# rev3.net
KiCad netlist of a schematic drawn in EAGLE
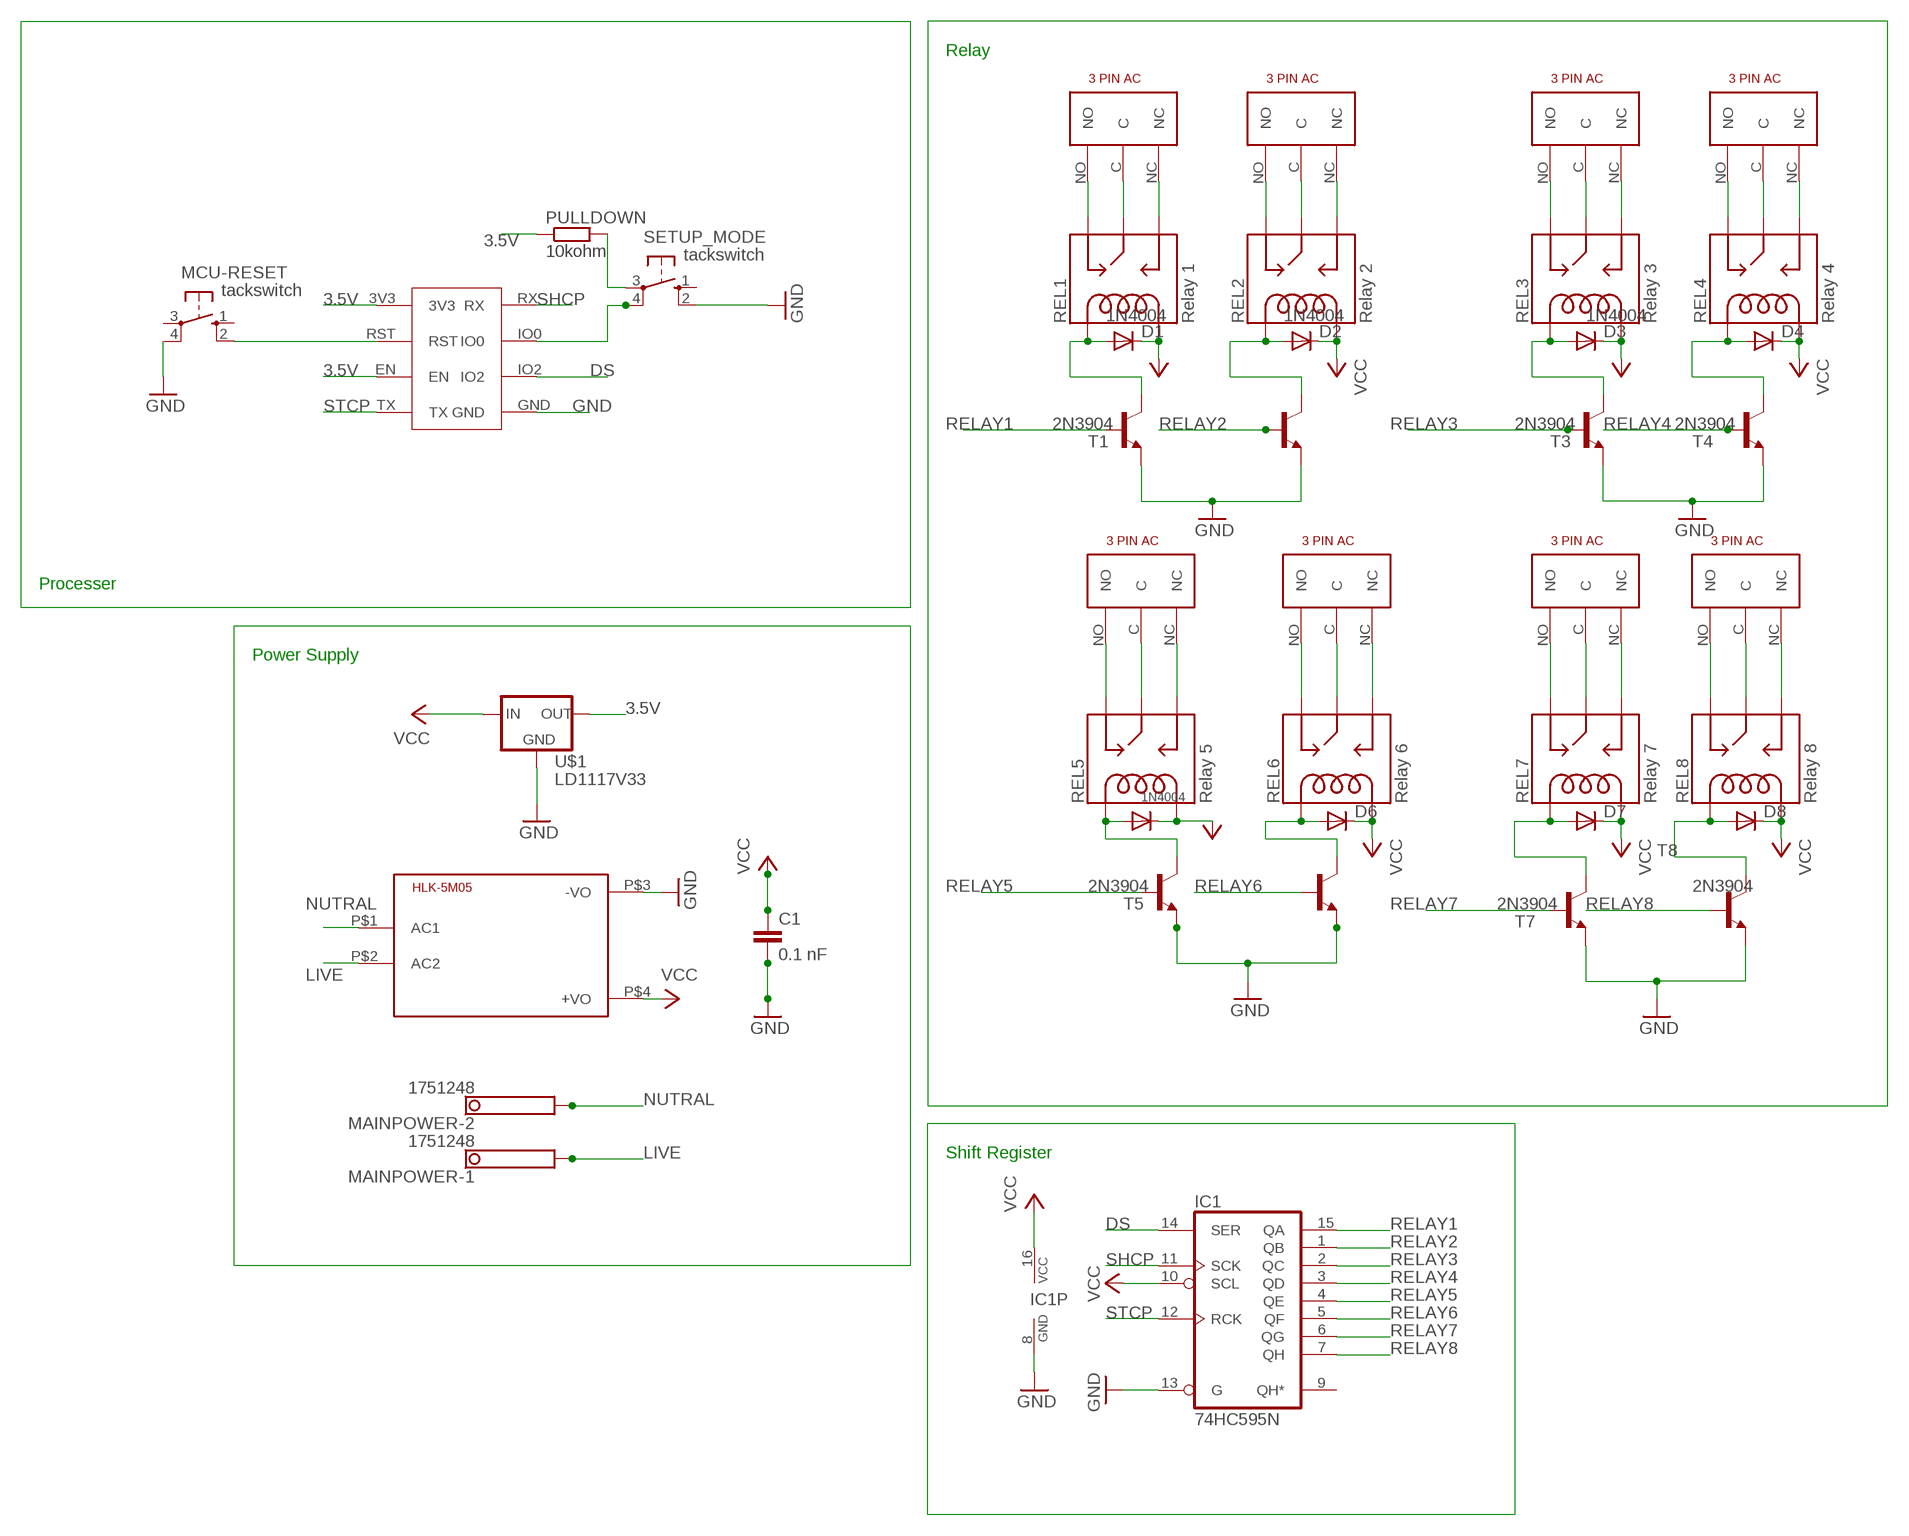
[diagram p0: schematic, sheet 1]

(export (version "E")
  (design (tool "Eeschema 10.0.6"))
  (components
    (comp (ref "C1")
      (value "0.1 nF")
      (footprint "eagle-import:CAP-PTH-SMALL-KIT")
      (libsource (lib "eagle-import") (part "0.1UF-KIT-EZ-50V-20%"))
    )
    (comp (ref "CON-REL-1")
      (value "3PINAC")
      (footprint "eagle-import:LIB")
      (libsource (lib "eagle-import") (part "3PINAC"))
    )
    (comp (ref "CON-REL-2")
      (value "3PINAC")
      (footprint "eagle-import:LIB")
      (libsource (lib "eagle-import") (part "3PINAC"))
    )
    (comp (ref "CON-REL-3")
      (value "3PINAC")
      (footprint "eagle-import:LIB")
      (libsource (lib "eagle-import") (part "3PINAC"))
    )
    (comp (ref "CON-REL-4")
      (value "3PINAC")
      (footprint "eagle-import:LIB")
      (libsource (lib "eagle-import") (part "3PINAC"))
    )
    (comp (ref "CON-REL-5")
      (value "3PINAC")
      (footprint "eagle-import:LIB")
      (libsource (lib "eagle-import") (part "3PINAC"))
    )
    (comp (ref "CON-REL-6")
      (value "3PINAC")
      (footprint "eagle-import:LIB")
      (libsource (lib "eagle-import") (part "3PINAC"))
    )
    (comp (ref "CON-REL-7")
      (value "3PINAC")
      (footprint "eagle-import:LIB")
      (libsource (lib "eagle-import") (part "3PINAC"))
    )
    (comp (ref "CON-REL-8")
      (value "3PINAC")
      (footprint "eagle-import:LIB")
      (libsource (lib "eagle-import") (part "3PINAC"))
    )
    (comp (ref "D1")
      (value "1N4004")
      (footprint "eagle-import:DO41-10")
      (libsource (lib "eagle-import") (part "1N4004"))
    )
    (comp (ref "D2")
      (value "1N4004")
      (footprint "eagle-import:DO41-10")
      (libsource (lib "eagle-import") (part "1N4004"))
    )
    (comp (ref "D3")
      (value "1N4004")
      (footprint "eagle-import:DO41-10")
      (libsource (lib "eagle-import") (part "1N4004"))
    )
    (comp (ref "D4")
      (value "1N4004")
      (footprint "eagle-import:DO41-10")
      (libsource (lib "eagle-import") (part "1N4004"))
    )
    (comp (ref "D5")
      (value "1N4004")
      (footprint "eagle-import:DO41-10")
      (libsource (lib "eagle-import") (part "1N4004"))
    )
    (comp (ref "D6")
      (value "1N4004")
      (footprint "eagle-import:DO41-10")
      (libsource (lib "eagle-import") (part "1N4004"))
    )
    (comp (ref "D7")
      (value "1N4004")
      (footprint "eagle-import:DO41-10")
      (libsource (lib "eagle-import") (part "1N4004"))
    )
    (comp (ref "D8")
      (value "1N4004")
      (footprint "eagle-import:DO41-10")
      (libsource (lib "eagle-import") (part "1N4004"))
    )
    (comp (ref "HLK-5M05")
      (value "AC to DC Converter")
      (footprint "eagle-import:HKLPM01")
      (libsource (lib "eagle-import") (part "HKLPM01"))
    )
    (comp (ref "IC1")
      (value "74HC595N")
      (footprint "eagle-import:DIL16")
      (libsource (lib "eagle-import") (part "74595NHC"))
    )
    (comp (ref "MAINPOWER")
      (value "1751248")
      (footprint "eagle-import:1751248")
      (libsource (lib "eagle-import") (part "1751248"))
    )
    (comp (ref "MCU-RESET")
      (value "tackswitch")
      (footprint "eagle-import:B3F-10XX")
      (libsource (lib "eagle-import") (part "10-XX"))
    )
    (comp (ref "PULLDOWN")
      (value "10kohm")
      (footprint "eagle-import:0204_7")
      (libsource (lib "eagle-import") (part "R-EU_0204/7"))
    )
    (comp (ref "REL1")
      (value "Relay 1")
      (footprint "eagle-import:SRD-05VDC-SL-C")
      (libsource (lib "eagle-import") (part "RELAYPTH"))
    )
    (comp (ref "REL2")
      (value "Relay 2")
      (footprint "eagle-import:SRD-05VDC-SL-C")
      (libsource (lib "eagle-import") (part "RELAYPTH"))
    )
    (comp (ref "REL3")
      (value "Relay 3")
      (footprint "eagle-import:SRD-05VDC-SL-C")
      (libsource (lib "eagle-import") (part "RELAYPTH"))
    )
    (comp (ref "REL4")
      (value "Relay 4")
      (footprint "eagle-import:SRD-05VDC-SL-C")
      (libsource (lib "eagle-import") (part "RELAYPTH"))
    )
    (comp (ref "REL5")
      (value "Relay 5")
      (footprint "eagle-import:SRD-05VDC-SL-C")
      (libsource (lib "eagle-import") (part "RELAYPTH"))
    )
    (comp (ref "REL6")
      (value "Relay 6")
      (footprint "eagle-import:SRD-05VDC-SL-C")
      (libsource (lib "eagle-import") (part "RELAYPTH"))
    )
    (comp (ref "REL7")
      (value "Relay 7")
      (footprint "eagle-import:SRD-05VDC-SL-C")
      (libsource (lib "eagle-import") (part "RELAYPTH"))
    )
    (comp (ref "REL8")
      (value "Relay 8")
      (footprint "eagle-import:SRD-05VDC-SL-C")
      (libsource (lib "eagle-import") (part "RELAYPTH"))
    )
    (comp (ref "SETUP_MODE")
      (value "tackswitch")
      (footprint "eagle-import:B3F-10XX")
      (libsource (lib "eagle-import") (part "10-XX"))
    )
    (comp (ref "T1")
      (value "2N3904")
      (footprint "eagle-import:TO92-EBC")
      (libsource (lib "eagle-import") (part "BC618"))
    )
    (comp (ref "T2")
      (value "2N3904")
      (footprint "eagle-import:TO92-EBC")
      (libsource (lib "eagle-import") (part "BC618"))
    )
    (comp (ref "T3")
      (value "2N3904")
      (footprint "eagle-import:TO92-EBC")
      (libsource (lib "eagle-import") (part "BC618"))
    )
    (comp (ref "T4")
      (value "2N3904")
      (footprint "eagle-import:TO92-EBC")
      (libsource (lib "eagle-import") (part "BC618"))
    )
    (comp (ref "T5")
      (value "2N3904")
      (footprint "eagle-import:TO92-EBC")
      (libsource (lib "eagle-import") (part "BC618"))
    )
    (comp (ref "T6")
      (value "2N3904")
      (footprint "eagle-import:TO92-EBC")
      (libsource (lib "eagle-import") (part "BC618"))
    )
    (comp (ref "T7")
      (value "2N3904")
      (footprint "eagle-import:TO92-EBC")
      (libsource (lib "eagle-import") (part "BC618"))
    )
    (comp (ref "T8")
      (value "2N3904")
      (footprint "eagle-import:TO92-EBC")
      (libsource (lib "eagle-import") (part "BC618"))
    )
    (comp (ref "U$1")
      (value "LD1117V33")
      (footprint "eagle-import:LD1117V33")
      (libsource (lib "eagle-import") (part "LD1117V33"))
    )
    (comp (ref "U$2")
      (value "ESP01")
      (footprint "eagle-import:ESP01")
      (libsource (lib "eagle-import") (part "ESP01"))
    )
  )
  (nets
    (net (code "1") (name "/3.5V") (class "Default")
      (node (ref "PULLDOWN") (pin "1") (pinfunction "1_1") (pintype "passive"))
      (node (ref "U$1") (pin "OUT") (pinfunction "OUT_OUT") (pintype "output"))
      (node (ref "U$2") (pin "3V3") (pinfunction "3V3_3V3") (pintype "bidirectional"))
      (node (ref "U$2") (pin "EN") (pinfunction "EN_EN") (pintype "bidirectional"))
    )
    (net (code "2") (name "/DS") (class "Default")
      (node (ref "IC1") (pin "14") (pinfunction "SER_14") (pintype "input"))
      (node (ref "U$2") (pin "IO2") (pinfunction "IO2_IO2") (pintype "bidirectional"))
    )
    (net (code "3") (name "/LIVE") (class "Default")
      (node (ref "HLK-5M05") (pin "P$2") (pinfunction "AC2_P$2") (pintype "bidirectional"))
      (node (ref "MAINPOWER") (pin "1") (pinfunction "K_1") (pintype "passive"))
    )
    (net (code "4") (name "/NUTRAL") (class "Default")
      (node (ref "HLK-5M05") (pin "P$1") (pinfunction "AC1_P$1") (pintype "bidirectional"))
      (node (ref "MAINPOWER") (pin "2") (pinfunction "K_2") (pintype "passive"))
    )
    (net (code "5") (name "/RELAY1") (class "Default")
      (node (ref "IC1") (pin "15") (pinfunction "QA_15") (pintype "tri_state"))
      (node (ref "T1") (pin "B") (pinfunction "B_B") (pintype "passive"))
    )
    (net (code "6") (name "/RELAY2") (class "Default")
      (node (ref "IC1") (pin "1") (pinfunction "QB_1") (pintype "tri_state"))
      (node (ref "T2") (pin "B") (pinfunction "B_B") (pintype "passive"))
    )
    (net (code "7") (name "/RELAY3") (class "Default")
      (node (ref "IC1") (pin "2") (pinfunction "QC_2") (pintype "tri_state"))
      (node (ref "T3") (pin "B") (pinfunction "B_B") (pintype "passive"))
    )
    (net (code "8") (name "/RELAY4") (class "Default")
      (node (ref "IC1") (pin "3") (pinfunction "QD_3") (pintype "tri_state"))
      (node (ref "T4") (pin "B") (pinfunction "B_B") (pintype "passive"))
    )
    (net (code "9") (name "/RELAY5") (class "Default")
      (node (ref "IC1") (pin "4") (pinfunction "QE_4") (pintype "tri_state"))
      (node (ref "T5") (pin "B") (pinfunction "B_B") (pintype "passive"))
    )
    (net (code "10") (name "/RELAY6") (class "Default")
      (node (ref "IC1") (pin "5") (pinfunction "QF_5") (pintype "tri_state"))
      (node (ref "T6") (pin "B") (pinfunction "B_B") (pintype "passive"))
    )
    (net (code "11") (name "/RELAY7") (class "Default")
      (node (ref "IC1") (pin "6") (pinfunction "QG_6") (pintype "tri_state"))
      (node (ref "T7") (pin "B") (pinfunction "B_B") (pintype "passive"))
    )
    (net (code "12") (name "/RELAY8") (class "Default")
      (node (ref "IC1") (pin "7") (pinfunction "QH_7") (pintype "tri_state"))
      (node (ref "T8") (pin "B") (pinfunction "B_B") (pintype "passive"))
    )
    (net (code "13") (name "/SHCP") (class "Default")
      (node (ref "IC1") (pin "11") (pinfunction "SCK_11") (pintype "input"))
      (node (ref "U$2") (pin "RX") (pinfunction "RX_RX") (pintype "bidirectional"))
    )
    (net (code "14") (name "/STCP") (class "Default")
      (node (ref "IC1") (pin "12") (pinfunction "RCK_12") (pintype "input"))
      (node (ref "U$2") (pin "TX") (pinfunction "TX_TX") (pintype "bidirectional"))
    )
    (net (code "15") (name "GND") (class "Default")
      (node (ref "C1") (pin "2") (pinfunction "2_2") (pintype "passive"))
      (node (ref "HLK-5M05") (pin "P$3") (pinfunction "-VO_P$3") (pintype "bidirectional"))
      (node (ref "IC1") (pin "13") (pinfunction "G_13") (pintype "input"))
      (node (ref "IC1") (pin "8") (pinfunction "GND_8") (pintype "power_in"))
      (node (ref "MCU-RESET") (pin "4") (pinfunction "P1_4") (pintype "passive"))
      (node (ref "SETUP_MODE") (pin "2") (pinfunction "S1_2") (pintype "passive"))
      (node (ref "T1") (pin "E") (pinfunction "E_E") (pintype "passive"))
      (node (ref "T2") (pin "E") (pinfunction "E_E") (pintype "passive"))
      (node (ref "T3") (pin "E") (pinfunction "E_E") (pintype "passive"))
      (node (ref "T4") (pin "E") (pinfunction "E_E") (pintype "passive"))
      (node (ref "T5") (pin "E") (pinfunction "E_E") (pintype "passive"))
      (node (ref "T6") (pin "E") (pinfunction "E_E") (pintype "passive"))
      (node (ref "T7") (pin "E") (pinfunction "E_E") (pintype "passive"))
      (node (ref "T8") (pin "E") (pinfunction "E_E") (pintype "passive"))
      (node (ref "U$1") (pin "GND") (pinfunction "GND_GND") (pintype "input"))
      (node (ref "U$2") (pin "GND") (pinfunction "GND_GND") (pintype "bidirectional"))
    )
    (net (code "16") (name "Net-(CON-REL-1-PadC)") (class "Default")
      (node (ref "CON-REL-1") (pin "C") (pinfunction "C_C") (pintype "bidirectional"))
      (node (ref "REL1") (pin "SWCOMMON") (pinfunction "SWCOMMON_SWCOMMON") (pintype "bidirectional"))
    )
    (net (code "17") (name "Net-(CON-REL-1-PadNC)") (class "Default")
      (node (ref "CON-REL-1") (pin "NC") (pinfunction "NC_NC") (pintype "bidirectional"))
      (node (ref "REL1") (pin "SWOPEN") (pinfunction "SWOPEN_SWOPEN") (pintype "bidirectional"))
    )
    (net (code "18") (name "Net-(CON-REL-2-PadC)") (class "Default")
      (node (ref "CON-REL-2") (pin "C") (pinfunction "C_C") (pintype "bidirectional"))
      (node (ref "REL2") (pin "SWCOMMON") (pinfunction "SWCOMMON_SWCOMMON") (pintype "bidirectional"))
    )
    (net (code "19") (name "Net-(CON-REL-2-PadNC)") (class "Default")
      (node (ref "CON-REL-2") (pin "NC") (pinfunction "NC_NC") (pintype "bidirectional"))
      (node (ref "REL2") (pin "SWOPEN") (pinfunction "SWOPEN_SWOPEN") (pintype "bidirectional"))
    )
    (net (code "20") (name "Net-(CON-REL-3-PadC)") (class "Default")
      (node (ref "CON-REL-3") (pin "C") (pinfunction "C_C") (pintype "bidirectional"))
      (node (ref "REL3") (pin "SWCOMMON") (pinfunction "SWCOMMON_SWCOMMON") (pintype "bidirectional"))
    )
    (net (code "21") (name "Net-(CON-REL-3-PadNC)") (class "Default")
      (node (ref "CON-REL-3") (pin "NC") (pinfunction "NC_NC") (pintype "bidirectional"))
      (node (ref "REL3") (pin "SWOPEN") (pinfunction "SWOPEN_SWOPEN") (pintype "bidirectional"))
    )
    (net (code "22") (name "Net-(CON-REL-4-PadC)") (class "Default")
      (node (ref "CON-REL-4") (pin "C") (pinfunction "C_C") (pintype "bidirectional"))
      (node (ref "REL4") (pin "SWCOMMON") (pinfunction "SWCOMMON_SWCOMMON") (pintype "bidirectional"))
    )
    (net (code "23") (name "Net-(CON-REL-4-PadNC)") (class "Default")
      (node (ref "CON-REL-4") (pin "NC") (pinfunction "NC_NC") (pintype "bidirectional"))
      (node (ref "REL4") (pin "SWOPEN") (pinfunction "SWOPEN_SWOPEN") (pintype "bidirectional"))
    )
    (net (code "24") (name "Net-(CON-REL-5-PadC)") (class "Default")
      (node (ref "CON-REL-5") (pin "C") (pinfunction "C_C") (pintype "bidirectional"))
      (node (ref "REL5") (pin "SWCOMMON") (pinfunction "SWCOMMON_SWCOMMON") (pintype "bidirectional"))
    )
    (net (code "25") (name "Net-(CON-REL-5-PadNC)") (class "Default")
      (node (ref "CON-REL-5") (pin "NC") (pinfunction "NC_NC") (pintype "bidirectional"))
      (node (ref "REL5") (pin "SWOPEN") (pinfunction "SWOPEN_SWOPEN") (pintype "bidirectional"))
    )
    (net (code "26") (name "Net-(CON-REL-6-PadC)") (class "Default")
      (node (ref "CON-REL-6") (pin "C") (pinfunction "C_C") (pintype "bidirectional"))
      (node (ref "REL6") (pin "SWCOMMON") (pinfunction "SWCOMMON_SWCOMMON") (pintype "bidirectional"))
    )
    (net (code "27") (name "Net-(CON-REL-6-PadNC)") (class "Default")
      (node (ref "CON-REL-6") (pin "NC") (pinfunction "NC_NC") (pintype "bidirectional"))
      (node (ref "REL6") (pin "SWOPEN") (pinfunction "SWOPEN_SWOPEN") (pintype "bidirectional"))
    )
    (net (code "28") (name "Net-(CON-REL-7-PadC)") (class "Default")
      (node (ref "CON-REL-7") (pin "C") (pinfunction "C_C") (pintype "bidirectional"))
      (node (ref "REL7") (pin "SWCOMMON") (pinfunction "SWCOMMON_SWCOMMON") (pintype "bidirectional"))
    )
    (net (code "29") (name "Net-(CON-REL-7-PadNC)") (class "Default")
      (node (ref "CON-REL-7") (pin "NC") (pinfunction "NC_NC") (pintype "bidirectional"))
      (node (ref "REL7") (pin "SWOPEN") (pinfunction "SWOPEN_SWOPEN") (pintype "bidirectional"))
    )
    (net (code "30") (name "Net-(CON-REL-8-PadC)") (class "Default")
      (node (ref "CON-REL-8") (pin "C") (pinfunction "C_C") (pintype "bidirectional"))
      (node (ref "REL8") (pin "SWCOMMON") (pinfunction "SWCOMMON_SWCOMMON") (pintype "bidirectional"))
    )
    (net (code "31") (name "Net-(CON-REL-8-PadNC)") (class "Default")
      (node (ref "CON-REL-8") (pin "NC") (pinfunction "NC_NC") (pintype "bidirectional"))
      (node (ref "REL8") (pin "SWOPEN") (pinfunction "SWOPEN_SWOPEN") (pintype "bidirectional"))
    )
    (net (code "32") (name "Net-(D1-PadA)") (class "Default")
      (node (ref "D1") (pin "A") (pinfunction "A_A") (pintype "passive"))
      (node (ref "REL1") (pin "COIL1") (pinfunction "COIL1_COIL1") (pintype "bidirectional"))
      (node (ref "T1") (pin "C") (pinfunction "C_C") (pintype "passive"))
    )
    (net (code "33") (name "Net-(D2-PadA)") (class "Default")
      (node (ref "D2") (pin "A") (pinfunction "A_A") (pintype "passive"))
      (node (ref "REL2") (pin "COIL1") (pinfunction "COIL1_COIL1") (pintype "bidirectional"))
      (node (ref "T2") (pin "C") (pinfunction "C_C") (pintype "passive"))
    )
    (net (code "34") (name "Net-(D3-PadA)") (class "Default")
      (node (ref "D3") (pin "A") (pinfunction "A_A") (pintype "passive"))
      (node (ref "REL3") (pin "COIL1") (pinfunction "COIL1_COIL1") (pintype "bidirectional"))
      (node (ref "T3") (pin "C") (pinfunction "C_C") (pintype "passive"))
    )
    (net (code "35") (name "Net-(D4-PadA)") (class "Default")
      (node (ref "D4") (pin "A") (pinfunction "A_A") (pintype "passive"))
      (node (ref "REL4") (pin "COIL1") (pinfunction "COIL1_COIL1") (pintype "bidirectional"))
      (node (ref "T4") (pin "C") (pinfunction "C_C") (pintype "passive"))
    )
    (net (code "36") (name "Net-(D5-PadA)") (class "Default")
      (node (ref "D5") (pin "A") (pinfunction "A_A") (pintype "passive"))
      (node (ref "REL5") (pin "COIL1") (pinfunction "COIL1_COIL1") (pintype "bidirectional"))
      (node (ref "T5") (pin "C") (pinfunction "C_C") (pintype "passive"))
    )
    (net (code "37") (name "Net-(D6-PadA)") (class "Default")
      (node (ref "D6") (pin "A") (pinfunction "A_A") (pintype "passive"))
      (node (ref "REL6") (pin "COIL1") (pinfunction "COIL1_COIL1") (pintype "bidirectional"))
      (node (ref "T6") (pin "C") (pinfunction "C_C") (pintype "passive"))
    )
    (net (code "38") (name "Net-(D7-PadA)") (class "Default")
      (node (ref "D7") (pin "A") (pinfunction "A_A") (pintype "passive"))
      (node (ref "REL7") (pin "COIL1") (pinfunction "COIL1_COIL1") (pintype "bidirectional"))
      (node (ref "T7") (pin "C") (pinfunction "C_C") (pintype "passive"))
    )
    (net (code "39") (name "Net-(D8-PadA)") (class "Default")
      (node (ref "D8") (pin "A") (pinfunction "A_A") (pintype "passive"))
      (node (ref "REL8") (pin "COIL1") (pinfunction "COIL1_COIL1") (pintype "bidirectional"))
      (node (ref "T8") (pin "C") (pinfunction "C_C") (pintype "passive"))
    )
    (net (code "40") (name "Net-(MCU-RESET-S1)") (class "Default")
      (node (ref "MCU-RESET") (pin "2") (pinfunction "S1_2") (pintype "passive"))
      (node (ref "U$2") (pin "RST") (pinfunction "RST_RST") (pintype "bidirectional"))
    )
    (net (code "41") (name "Net-(REL1-SWCLOSE)") (class "Default")
      (node (ref "CON-REL-1") (pin "NO") (pinfunction "NO_NO") (pintype "bidirectional"))
      (node (ref "REL1") (pin "SWCLOSED") (pinfunction "SWCLOSE_SWCLOSED") (pintype "bidirectional"))
    )
    (net (code "42") (name "Net-(REL2-SWCLOSE)") (class "Default")
      (node (ref "CON-REL-2") (pin "NO") (pinfunction "NO_NO") (pintype "bidirectional"))
      (node (ref "REL2") (pin "SWCLOSED") (pinfunction "SWCLOSE_SWCLOSED") (pintype "bidirectional"))
    )
    (net (code "43") (name "Net-(REL3-SWCLOSE)") (class "Default")
      (node (ref "CON-REL-3") (pin "NO") (pinfunction "NO_NO") (pintype "bidirectional"))
      (node (ref "REL3") (pin "SWCLOSED") (pinfunction "SWCLOSE_SWCLOSED") (pintype "bidirectional"))
    )
    (net (code "44") (name "Net-(REL4-SWCLOSE)") (class "Default")
      (node (ref "CON-REL-4") (pin "NO") (pinfunction "NO_NO") (pintype "bidirectional"))
      (node (ref "REL4") (pin "SWCLOSED") (pinfunction "SWCLOSE_SWCLOSED") (pintype "bidirectional"))
    )
    (net (code "45") (name "Net-(REL5-SWCLOSE)") (class "Default")
      (node (ref "CON-REL-5") (pin "NO") (pinfunction "NO_NO") (pintype "bidirectional"))
      (node (ref "REL5") (pin "SWCLOSED") (pinfunction "SWCLOSE_SWCLOSED") (pintype "bidirectional"))
    )
    (net (code "46") (name "Net-(REL6-SWCLOSE)") (class "Default")
      (node (ref "CON-REL-6") (pin "NO") (pinfunction "NO_NO") (pintype "bidirectional"))
      (node (ref "REL6") (pin "SWCLOSED") (pinfunction "SWCLOSE_SWCLOSED") (pintype "bidirectional"))
    )
    (net (code "47") (name "Net-(REL7-SWCLOSE)") (class "Default")
      (node (ref "CON-REL-7") (pin "NO") (pinfunction "NO_NO") (pintype "bidirectional"))
      (node (ref "REL7") (pin "SWCLOSED") (pinfunction "SWCLOSE_SWCLOSED") (pintype "bidirectional"))
    )
    (net (code "48") (name "Net-(REL8-SWCLOSE)") (class "Default")
      (node (ref "CON-REL-8") (pin "NO") (pinfunction "NO_NO") (pintype "bidirectional"))
      (node (ref "REL8") (pin "SWCLOSED") (pinfunction "SWCLOSE_SWCLOSED") (pintype "bidirectional"))
    )
    (net (code "49") (name "Net-(SETUP_MODE-P)") (class "Default")
      (node (ref "PULLDOWN") (pin "2") (pinfunction "2_2") (pintype "passive"))
      (node (ref "SETUP_MODE") (pin "3") (pinfunction "P_3") (pintype "passive"))
    )
    (net (code "50") (name "Net-(SETUP_MODE-P1)") (class "Default")
      (node (ref "SETUP_MODE") (pin "4") (pinfunction "P1_4") (pintype "passive"))
      (node (ref "U$2") (pin "IO0") (pinfunction "IO0_IO0") (pintype "bidirectional"))
    )
    (net (code "51") (name "VCC") (class "Default")
      (node (ref "C1") (pin "1") (pinfunction "1_1") (pintype "passive"))
      (node (ref "D1") (pin "C") (pinfunction "C_C") (pintype "passive"))
      (node (ref "D2") (pin "C") (pinfunction "C_C") (pintype "passive"))
      (node (ref "D3") (pin "C") (pinfunction "C_C") (pintype "passive"))
      (node (ref "D4") (pin "C") (pinfunction "C_C") (pintype "passive"))
      (node (ref "D5") (pin "C") (pinfunction "C_C") (pintype "passive"))
      (node (ref "D6") (pin "C") (pinfunction "C_C") (pintype "passive"))
      (node (ref "D7") (pin "C") (pinfunction "C_C") (pintype "passive"))
      (node (ref "D8") (pin "C") (pinfunction "C_C") (pintype "passive"))
      (node (ref "HLK-5M05") (pin "P$4") (pinfunction "+VO_P$4") (pintype "bidirectional"))
      (node (ref "IC1") (pin "10") (pinfunction "SCL_10") (pintype "input"))
      (node (ref "IC1") (pin "16") (pinfunction "VCC_16") (pintype "power_in"))
      (node (ref "REL1") (pin "COIL0") (pinfunction "COIL0_COIL0") (pintype "bidirectional"))
      (node (ref "REL2") (pin "COIL0") (pinfunction "COIL0_COIL0") (pintype "bidirectional"))
      (node (ref "REL3") (pin "COIL0") (pinfunction "COIL0_COIL0") (pintype "bidirectional"))
      (node (ref "REL4") (pin "COIL0") (pinfunction "COIL0_COIL0") (pintype "bidirectional"))
      (node (ref "REL5") (pin "COIL0") (pinfunction "COIL0_COIL0") (pintype "bidirectional"))
      (node (ref "REL6") (pin "COIL0") (pinfunction "COIL0_COIL0") (pintype "bidirectional"))
      (node (ref "REL7") (pin "COIL0") (pinfunction "COIL0_COIL0") (pintype "bidirectional"))
      (node (ref "REL8") (pin "COIL0") (pinfunction "COIL0_COIL0") (pintype "bidirectional"))
      (node (ref "U$1") (pin "IN") (pinfunction "IN_IN") (pintype "input"))
    )
    (net (code "52") (name "unconnected-(IC1A-QH*-Pad9)") (class "Default")
      (node (ref "IC1") (pin "9") (pinfunction "QH*_9") (pintype "tri_state"))
    )
    (net (code "53") (name "unconnected-(MCU-RESET-P-Pad3)") (class "Default")
      (node (ref "MCU-RESET") (pin "3") (pinfunction "P_3") (pintype "passive"))
    )
    (net (code "54") (name "unconnected-(MCU-RESET-S-Pad1)") (class "Default")
      (node (ref "MCU-RESET") (pin "1") (pinfunction "S_1") (pintype "passive"))
    )
    (net (code "55") (name "unconnected-(SETUP_MODE-S-Pad1)") (class "Default")
      (node (ref "SETUP_MODE") (pin "1") (pinfunction "S_1") (pintype "passive"))
    )
  )
)
